# Sheet1.net
KiCad netlist of a schematic drawn in Altium Designer
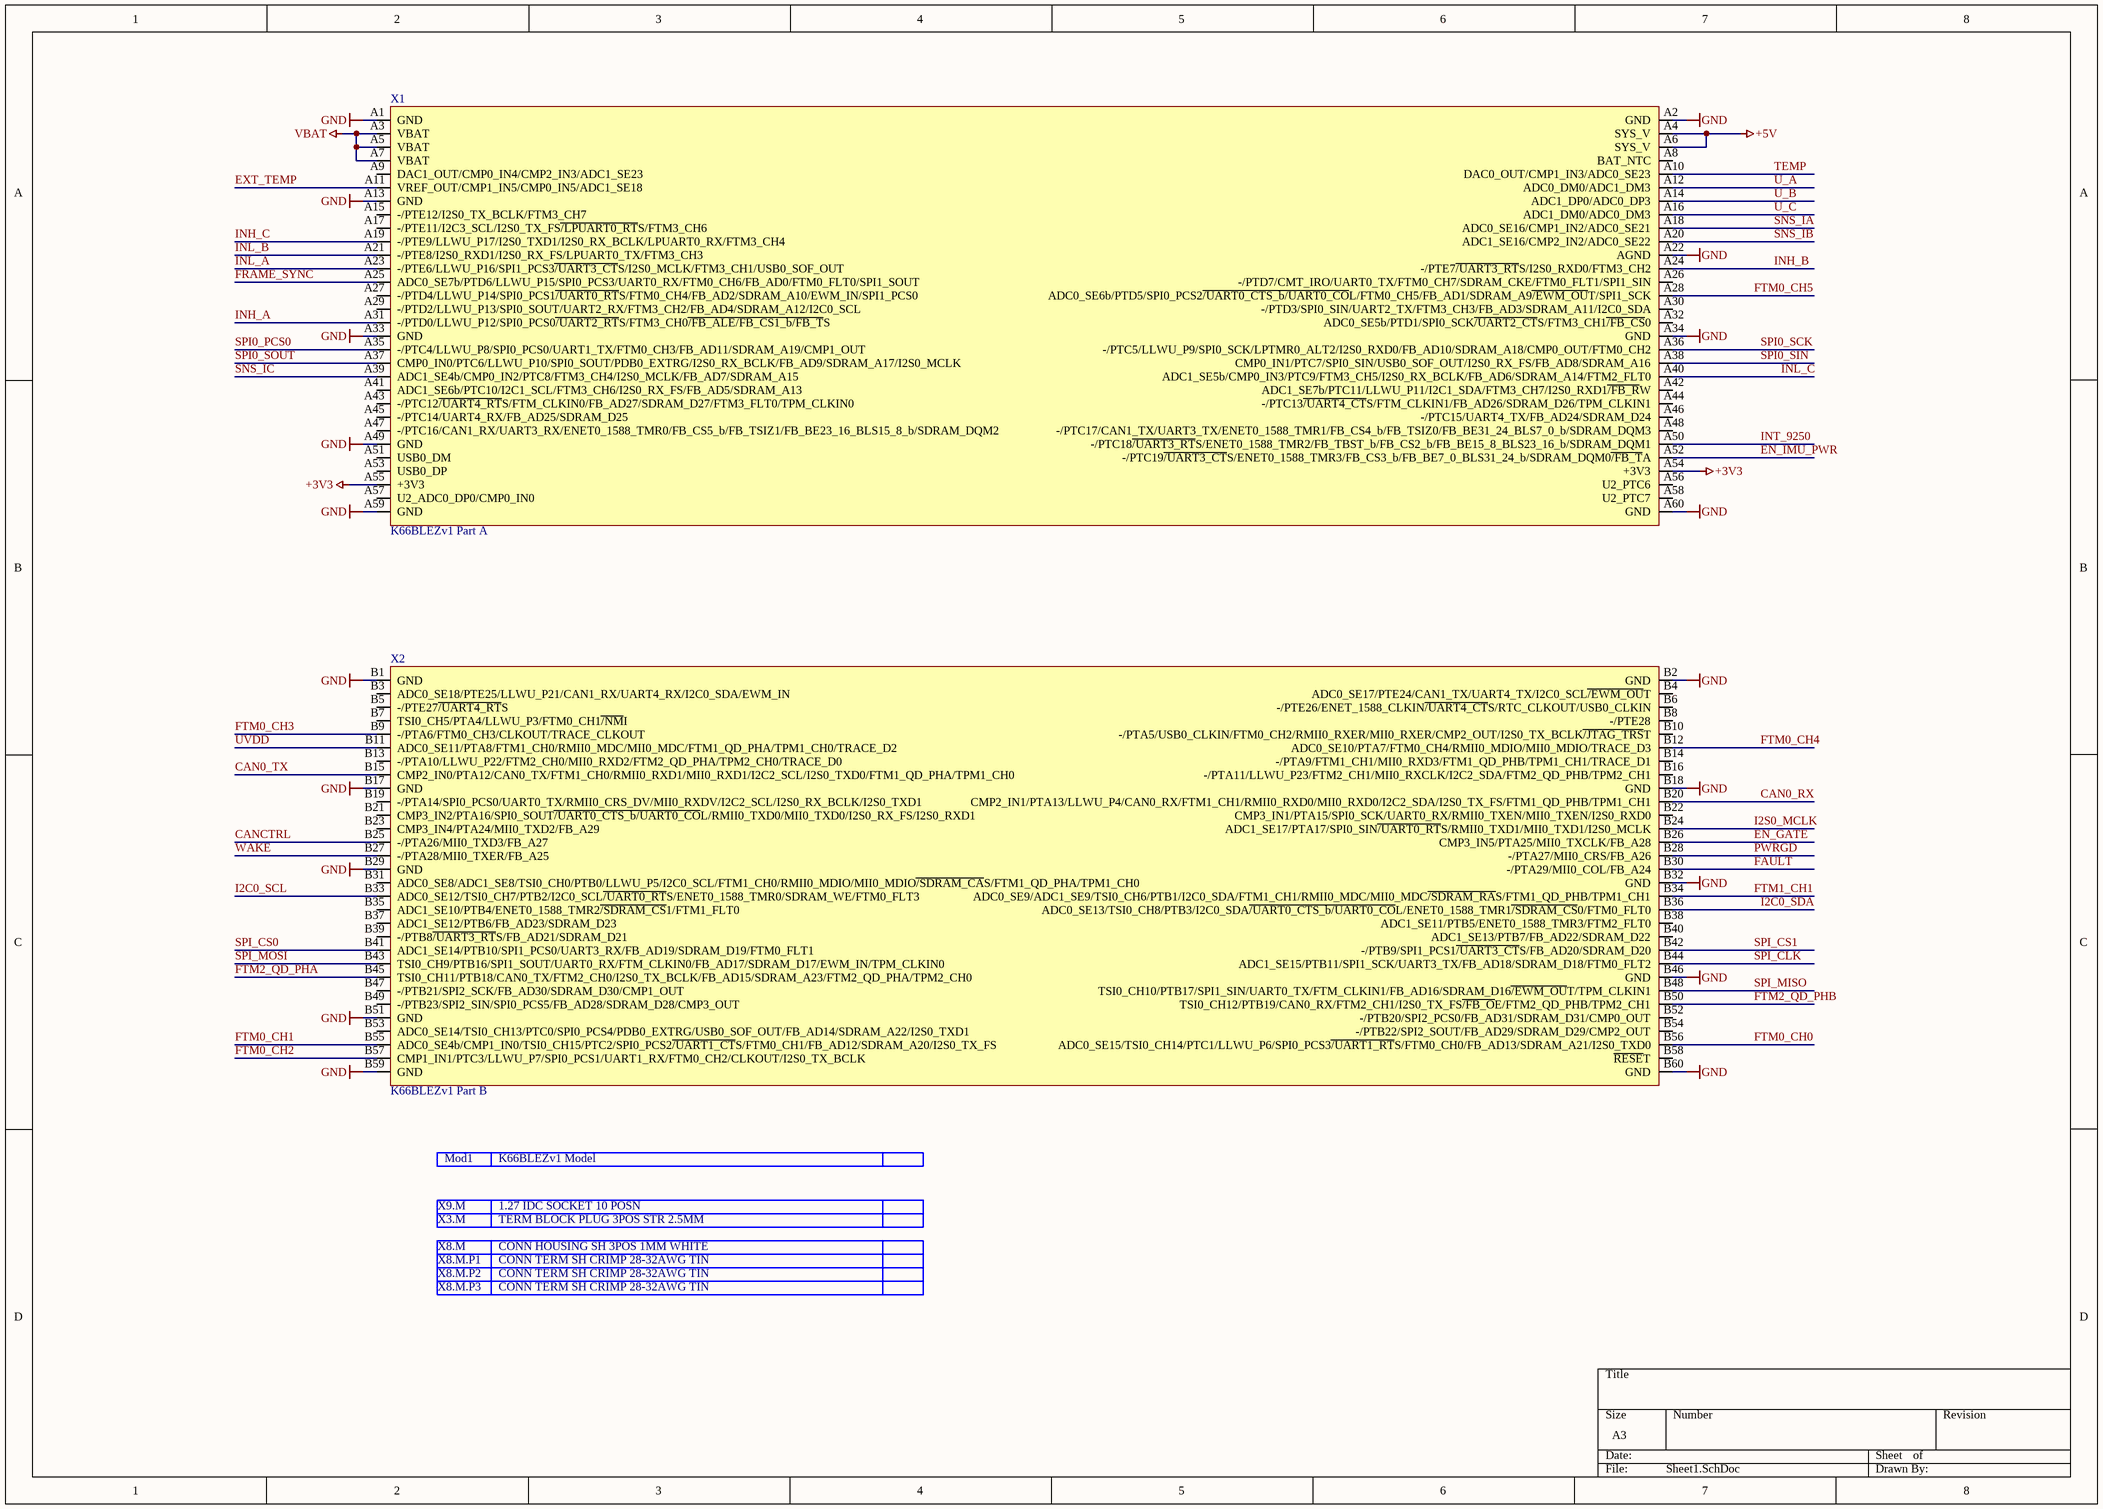
[diagram p0: Sheet1.SchDoc]

(export (version "E")
  (design (tool "Eeschema 10.0.6"))
  (components
    (comp (ref "Mod1")
      (value "K66BLEZv1 Model")
      (footprint "K66BLEZv1.0 Mechanical")
      (libsource (lib "K66BLEZ1") (part "K66BLEZv1 Model"))
    )
    (comp (ref "X1")
      (value "K66BLEZv1 Part A")
      (footprint "K66BLEZv1.0 Part A")
      (description "60 Position Connector Header, Outer Shroud Contacts Surface Mount Gold")
      (fields (field (name "MANUFACTURER") "Hirose Electric Co Ltd") (field (name "PARTNUM") "H10787-ND"))
      (libsource (lib "K66BLEZ1") (part "K66BLEZv1 Part A"))
    )
    (comp (ref "X2")
      (value "K66BLEZv1 Part B")
      (footprint "K66BLEZv1.0 Part B")
      (description "60 Position Connector Header, Outer Shroud Contacts Surface Mount Gold")
      (fields (field (name "MANUFACTURER") "Hirose Electric Co Ltd") (field (name "PARTNUM") "H10787-ND"))
      (libsource (lib "K66BLEZ1") (part "K66BLEZv1 Part B"))
    )
    (comp (ref "X3.M")
      (value "TERM BLOCK PLUG 3POS STR 2.5MM")
      (description "3 Position Terminal Block Plug, Female Sockets 0.098\" (2.50mm) 180° Free Hanging (In-Line)")
      (fields (field (name "MANUFACTURER") "Phoenix Contact") (field (name "PARTNUM") "277-11811-ND"))
      (libsource (lib "ea_Mechanical") (part "BOM item"))
    )
    (comp (ref "X8.M")
      (value "CONN HOUSING SH 3POS 1MM WHITE")
      (description "3 Position Rectangular Housing Connector Receptacle Natural 0.039\" (1.00mm)")
      (fields (field (name "MANUFACTURER") "JST Sales America Inc.") (field (name "PARTNUM") "455-1393-ND"))
      (libsource (lib "ea_Mechanical") (part "BOM item"))
    )
    (comp (ref "X8.M.P1")
      (value "CONN TERM SH CRIMP 28-32AWG TIN")
      (description "Contact Crimp Socket 28-32 AWG Tin")
      (fields (field (name "MANUFACTURER") "JST Sales America Inc.") (field (name "PARTNUM") "455-1561-1-ND"))
      (libsource (lib "ea_Mechanical") (part "BOM item"))
    )
    (comp (ref "X8.M.P2")
      (value "CONN TERM SH CRIMP 28-32AWG TIN")
      (description "Contact Crimp Socket 28-32 AWG Tin")
      (fields (field (name "MANUFACTURER") "JST Sales America Inc.") (field (name "PARTNUM") "455-1561-1-ND"))
      (libsource (lib "ea_Mechanical") (part "BOM item"))
    )
    (comp (ref "X8.M.P3")
      (value "CONN TERM SH CRIMP 28-32AWG TIN")
      (description "Contact Crimp Socket 28-32 AWG Tin")
      (fields (field (name "MANUFACTURER") "JST Sales America Inc.") (field (name "PARTNUM") "455-1561-1-ND"))
      (libsource (lib "ea_Mechanical") (part "BOM item"))
    )
    (comp (ref "X9.M")
      (value "1.27 IDC SOCKET 10 POSN")
      (description "10 Position Rectangular Receptacle Connector IDC Gold 30 AWG")
      (fields (field (name "MANUFACTURER") "CNC Tech") (field (name "PARTNUM") "1175-1645-ND"))
      (libsource (lib "ea_Mechanical") (part "BOM item"))
    )
  )
  (nets
    (net (code "1") (name "+3V3") (class "Default")
      (node (ref "X1") (pin "A54") (pinfunction "+3V3_A54") (pintype "passive"))
      (node (ref "X1") (pin "A55") (pinfunction "+3V3_A55") (pintype "passive"))
    )
    (net (code "2") (name "+5V") (class "Default")
      (node (ref "X1") (pin "A4") (pinfunction "SYS_V_A4") (pintype "passive"))
      (node (ref "X1") (pin "A6") (pinfunction "SYS_V_A6") (pintype "passive"))
    )
    (net (code "3") (name "/CAN0_RX") (class "Default")
      (node (ref "X2") (pin "B20") (pinfunction "CMP2_IN1/PTA13/LLWU_P4/CAN0_RX/FTM1_CH1/RMII0_RXD0/MII0_RXD0/I2C2_SDA/I2S0_TX_FS/FTM1_QD_PHB/TPM1_CH1_B20") (pintype "bidirectional"))
    )
    (net (code "4") (name "/CAN0_TX") (class "Default")
      (node (ref "X2") (pin "B15") (pinfunction "CMP2_IN0/PTA12/CAN0_TX/FTM1_CH0/RMII0_RXD1/MII0_RXD1/I2C2_SCL/I2S0_TXD0/FTM1_QD_PHA/TPM1_CH0_B15") (pintype "bidirectional"))
    )
    (net (code "5") (name "/CANCTRL") (class "Default")
      (node (ref "X2") (pin "B25") (pinfunction "-/PTA26/MII0_TXD3/FB_A27_B25") (pintype "bidirectional"))
    )
    (net (code "6") (name "/EN_GATE") (class "Default")
      (node (ref "X2") (pin "B26") (pinfunction "CMP3_IN5/PTA25/MII0_TXCLK/FB_A28_B26") (pintype "bidirectional"))
    )
    (net (code "7") (name "/EN_IMU_PWR") (class "Default")
      (node (ref "X1") (pin "A52") (pinfunction "-/PTC19~{/UART3_CT}S/ENET0_1588_TMR3/FB_CS3_b/FB_BE7_0_BLS31_24_b/SDRAM_DQM0~{/FB_T}A_A52") (pintype "bidirectional"))
    )
    (net (code "8") (name "/EXT_TEMP") (class "Default")
      (node (ref "X1") (pin "A11") (pinfunction "VREF_OUT/CMP1_IN5/CMP0_IN5/ADC1_SE18_A11") (pintype "bidirectional"))
    )
    (net (code "9") (name "/FAULT") (class "Default")
      (node (ref "X2") (pin "B30") (pinfunction "-/PTA29/MII0_COL/FB_A24_B30") (pintype "bidirectional"))
    )
    (net (code "10") (name "/FRAME_SYNC") (class "Default")
      (node (ref "X1") (pin "A25") (pinfunction "ADC0_SE7b/PTD6/LLWU_P15/SPI0_PCS3/UART0_RX/FTM0_CH6/FB_AD0/FTM0_FLT0/SPI1_SOUT_A25") (pintype "bidirectional"))
    )
    (net (code "11") (name "/FTM0_CH0") (class "Default")
      (node (ref "X2") (pin "B56") (pinfunction "ADC0_SE15/TSI0_CH14/PTC1/LLWU_P6/SPI0_PCS3~{/UART1_RT}S/FTM0_CH0/FB_AD13/SDRAM_A21/I2S0_TXD0_B56") (pintype "bidirectional"))
    )
    (net (code "12") (name "/FTM0_CH1") (class "Default")
      (node (ref "X2") (pin "B55") (pinfunction "ADC0_SE4b/CMP1_IN0/TSI0_CH15/PTC2/SPI0_PCS2~{/UART1_CT}S/FTM0_CH1/FB_AD12/SDRAM_A20/I2S0_TX_FS_B55") (pintype "bidirectional"))
    )
    (net (code "13") (name "/FTM0_CH2") (class "Default")
      (node (ref "X2") (pin "B57") (pinfunction "CMP1_IN1/PTC3/LLWU_P7/SPI0_PCS1/UART1_RX/FTM0_CH2/CLKOUT/I2S0_TX_BCLK_B57") (pintype "bidirectional"))
    )
    (net (code "14") (name "/FTM0_CH3") (class "Default")
      (node (ref "X2") (pin "B9") (pinfunction "-/PTA6/FTM0_CH3/CLKOUT/TRACE_CLKOUT_B9") (pintype "bidirectional"))
    )
    (net (code "15") (name "/FTM0_CH4") (class "Default")
      (node (ref "X2") (pin "B12") (pinfunction "ADC0_SE10/PTA7/FTM0_CH4/RMII0_MDIO/MII0_MDIO/TRACE_D3_B12") (pintype "bidirectional"))
    )
    (net (code "16") (name "/FTM0_CH5") (class "Default")
      (node (ref "X1") (pin "A28") (pinfunction "ADC0_SE6b/PTD5/SPI0_PCS2~{/UART0_CTS_b/UART0_CO}L/FTM0_CH5/FB_AD1/SDRAM_A9~{/EWM_OU}T/SPI1_SCK_A28") (pintype "bidirectional"))
    )
    (net (code "17") (name "/FTM1_CH1") (class "Default")
      (node (ref "X2") (pin "B34") (pinfunction "ADC0_SE9/ADC1_SE9/TSI0_CH6/PTB1/I2C0_SDA/FTM1_CH1/RMII0_MDC/MII0_MDC~{/SDRAM_RA}S/FTM1_QD_PHB/TPM1_CH1_B34") (pintype "bidirectional"))
    )
    (net (code "18") (name "/FTM2_QD_PHA") (class "Default")
      (node (ref "X2") (pin "B45") (pinfunction "TSI0_CH11/PTB18/CAN0_TX/FTM2_CH0/I2S0_TX_BCLK/FB_AD15/SDRAM_A23/FTM2_QD_PHA/TPM2_CH0_B45") (pintype "bidirectional"))
    )
    (net (code "19") (name "/FTM2_QD_PHB") (class "Default")
      (node (ref "X2") (pin "B50") (pinfunction "TSI0_CH12/PTB19/CAN0_RX/FTM2_CH1/I2S0_TX_FS~{/FB_O}E/FTM2_QD_PHB/TPM2_CH1_B50") (pintype "bidirectional"))
    )
    (net (code "20") (name "/I2C0_SCL") (class "Default")
      (node (ref "X2") (pin "B33") (pinfunction "ADC0_SE12/TSI0_CH7/PTB2/I2C0_SCL~{/UART0_RT}S/ENET0_1588_TMR0/SDRAM_WE/FTM0_FLT3_B33") (pintype "bidirectional"))
    )
    (net (code "21") (name "/I2C0_SDA") (class "Default")
      (node (ref "X2") (pin "B36") (pinfunction "ADC0_SE13/TSI0_CH8/PTB3/I2C0_SDA~{/UART0_CTS_b/UART0_CO}L/ENET0_1588_TMR1~{/SDRAM_CS}0/FTM0_FLT0_B36") (pintype "bidirectional"))
    )
    (net (code "22") (name "/I2S0_MCLK") (class "Default")
      (node (ref "X2") (pin "B24") (pinfunction "ADC1_SE17/PTA17/SPI0_SIN~{/UART0_RT}S/RMII0_TXD1/MII0_TXD1/I2S0_MCLK_B24") (pintype "bidirectional"))
    )
    (net (code "23") (name "/INH_A") (class "Default")
      (node (ref "X1") (pin "A31") (pinfunction "-/PTD0/LLWU_P12/SPI0_PCS0~{/UART2_RT}S/FTM3_CH0~{/FB_ALE/FB_CS1_b/FB_T}S_A31") (pintype "bidirectional"))
    )
    (net (code "24") (name "/INH_B") (class "Default")
      (node (ref "X1") (pin "A24") (pinfunction "-/PTE7~{/UART3_RT}S/I2S0_RXD0/FTM3_CH2_A24") (pintype "bidirectional"))
    )
    (net (code "25") (name "/INH_C") (class "Default")
      (node (ref "X1") (pin "A19") (pinfunction "-/PTE9/LLWU_P17/I2S0_TXD1/I2S0_RX_BCLK/LPUART0_RX/FTM3_CH4_A19") (pintype "bidirectional"))
    )
    (net (code "26") (name "/INL_A") (class "Default")
      (node (ref "X1") (pin "A23") (pinfunction "-/PTE6/LLWU_P16/SPI1_PCS3~{/UART3_CT}S/I2S0_MCLK/FTM3_CH1/USB0_SOF_OUT_A23") (pintype "bidirectional"))
    )
    (net (code "27") (name "/INL_B") (class "Default")
      (node (ref "X1") (pin "A21") (pinfunction "-/PTE8/I2S0_RXD1/I2S0_RX_FS/LPUART0_TX/FTM3_CH3_A21") (pintype "bidirectional"))
    )
    (net (code "28") (name "/INL_C") (class "Default")
      (node (ref "X1") (pin "A40") (pinfunction "ADC1_SE5b/CMP0_IN3/PTC9/FTM3_CH5/I2S0_RX_BCLK/FB_AD6/SDRAM_A14/FTM2_FLT0_A40") (pintype "bidirectional"))
    )
    (net (code "29") (name "/INT_9250") (class "Default")
      (node (ref "X1") (pin "A50") (pinfunction "-/PTC18~{/UART3_RT}S/ENET0_1588_TMR2/FB_TBST_b/FB_CS2_b/FB_BE15_8_BLS23_16_b/SDRAM_DQM1_A50") (pintype "bidirectional"))
    )
    (net (code "30") (name "/PWRGD") (class "Default")
      (node (ref "X2") (pin "B28") (pinfunction "-/PTA27/MII0_CRS/FB_A26_B28") (pintype "bidirectional"))
    )
    (net (code "31") (name "/SNS_IA") (class "Default")
      (node (ref "X1") (pin "A18") (pinfunction "ADC0_SE16/CMP1_IN2/ADC0_SE21_A18") (pintype "bidirectional"))
    )
    (net (code "32") (name "/SNS_IB") (class "Default")
      (node (ref "X1") (pin "A20") (pinfunction "ADC1_SE16/CMP2_IN2/ADC0_SE22_A20") (pintype "bidirectional"))
    )
    (net (code "33") (name "/SNS_IC") (class "Default")
      (node (ref "X1") (pin "A39") (pinfunction "ADC1_SE4b/CMP0_IN2/PTC8/FTM3_CH4/I2S0_MCLK/FB_AD7/SDRAM_A15_A39") (pintype "bidirectional"))
    )
    (net (code "34") (name "/SPI0_PCS0") (class "Default")
      (node (ref "X1") (pin "A35") (pinfunction "-/PTC4/LLWU_P8/SPI0_PCS0/UART1_TX/FTM0_CH3/FB_AD11/SDRAM_A19/CMP1_OUT_A35") (pintype "bidirectional"))
    )
    (net (code "35") (name "/SPI0_SCK") (class "Default")
      (node (ref "X1") (pin "A36") (pinfunction "-/PTC5/LLWU_P9/SPI0_SCK/LPTMR0_ALT2/I2S0_RXD0/FB_AD10/SDRAM_A18/CMP0_OUT/FTM0_CH2_A36") (pintype "bidirectional"))
    )
    (net (code "36") (name "/SPI0_SIN") (class "Default")
      (node (ref "X1") (pin "A38") (pinfunction "CMP0_IN1/PTC7/SPI0_SIN/USB0_SOF_OUT/I2S0_RX_FS/FB_AD8/SDRAM_A16_A38") (pintype "bidirectional"))
    )
    (net (code "37") (name "/SPI0_SOUT") (class "Default")
      (node (ref "X1") (pin "A37") (pinfunction "CMP0_IN0/PTC6/LLWU_P10/SPI0_SOUT/PDB0_EXTRG/I2S0_RX_BCLK/FB_AD9/SDRAM_A17/I2S0_MCLK_A37") (pintype "bidirectional"))
    )
    (net (code "38") (name "/SPI_CLK") (class "Default")
      (node (ref "X2") (pin "B44") (pinfunction "ADC1_SE15/PTB11/SPI1_SCK/UART3_TX/FB_AD18/SDRAM_D18/FTM0_FLT2_B44") (pintype "bidirectional"))
    )
    (net (code "39") (name "/SPI_CS0") (class "Default")
      (node (ref "X2") (pin "B41") (pinfunction "ADC1_SE14/PTB10/SPI1_PCS0/UART3_RX/FB_AD19/SDRAM_D19/FTM0_FLT1_B41") (pintype "bidirectional"))
    )
    (net (code "40") (name "/SPI_CS1") (class "Default")
      (node (ref "X2") (pin "B42") (pinfunction "-/PTB9/SPI1_PCS1~{/UART3_CT}S/FB_AD20/SDRAM_D20_B42") (pintype "bidirectional"))
    )
    (net (code "41") (name "/SPI_MISO") (class "Default")
      (node (ref "X2") (pin "B48") (pinfunction "TSI0_CH10/PTB17/SPI1_SIN/UART0_TX/FTM_CLKIN1/FB_AD16/SDRAM_D16~{/EWM_OU}T/TPM_CLKIN1_B48") (pintype "bidirectional"))
    )
    (net (code "42") (name "/SPI_MOSI") (class "Default")
      (node (ref "X2") (pin "B43") (pinfunction "TSI0_CH9/PTB16/SPI1_SOUT/UART0_RX/FTM_CLKIN0/FB_AD17/SDRAM_D17/EWM_IN/TPM_CLKIN0_B43") (pintype "bidirectional"))
    )
    (net (code "43") (name "/TEMP") (class "Default")
      (node (ref "X1") (pin "A10") (pinfunction "DAC0_OUT/CMP1_IN3/ADC0_SE23_A10") (pintype "bidirectional"))
    )
    (net (code "44") (name "/UVDD") (class "Default")
      (node (ref "X2") (pin "B11") (pinfunction "ADC0_SE11/PTA8/FTM1_CH0/RMII0_MDC/MII0_MDC/FTM1_QD_PHA/TPM1_CH0/TRACE_D2_B11") (pintype "bidirectional"))
    )
    (net (code "45") (name "/U_A") (class "Default")
      (node (ref "X1") (pin "A12") (pinfunction "ADC0_DM0/ADC1_DM3_A12") (pintype "bidirectional"))
    )
    (net (code "46") (name "/U_B") (class "Default")
      (node (ref "X1") (pin "A14") (pinfunction "ADC1_DP0/ADC0_DP3_A14") (pintype "bidirectional"))
    )
    (net (code "47") (name "/U_C") (class "Default")
      (node (ref "X1") (pin "A16") (pinfunction "ADC1_DM0/ADC0_DM3_A16") (pintype "bidirectional"))
    )
    (net (code "48") (name "/WAKE") (class "Default")
      (node (ref "X2") (pin "B27") (pinfunction "-/PTA28/MII0_TXER/FB_A25_B27") (pintype "bidirectional"))
    )
    (net (code "49") (name "GND") (class "Default")
      (node (ref "X1") (pin "A1") (pinfunction "GND_A1") (pintype "passive"))
      (node (ref "X1") (pin "A13") (pinfunction "GND_A13") (pintype "passive"))
      (node (ref "X1") (pin "A2") (pinfunction "GND_A2") (pintype "passive"))
      (node (ref "X1") (pin "A22") (pinfunction "AGND_A22") (pintype "passive"))
      (node (ref "X1") (pin "A33") (pinfunction "GND_A33") (pintype "passive"))
      (node (ref "X1") (pin "A34") (pinfunction "GND_A34") (pintype "passive"))
      (node (ref "X1") (pin "A49") (pinfunction "GND_A49") (pintype "passive"))
      (node (ref "X1") (pin "A59") (pinfunction "GND_A59") (pintype "passive"))
      (node (ref "X1") (pin "A60") (pinfunction "GND_A60") (pintype "passive"))
      (node (ref "X2") (pin "B1") (pinfunction "GND_B1") (pintype "passive"))
      (node (ref "X2") (pin "B17") (pinfunction "GND_B17") (pintype "passive"))
      (node (ref "X2") (pin "B18") (pinfunction "GND_B18") (pintype "passive"))
      (node (ref "X2") (pin "B2") (pinfunction "GND_B2") (pintype "passive"))
      (node (ref "X2") (pin "B29") (pinfunction "GND_B29") (pintype "passive"))
      (node (ref "X2") (pin "B32") (pinfunction "GND_B32") (pintype "passive"))
      (node (ref "X2") (pin "B46") (pinfunction "GND_B46") (pintype "passive"))
      (node (ref "X2") (pin "B51") (pinfunction "GND_B51") (pintype "passive"))
      (node (ref "X2") (pin "B59") (pinfunction "GND_B59") (pintype "passive"))
      (node (ref "X2") (pin "B60") (pinfunction "GND_B60") (pintype "passive"))
    )
    (net (code "50") (name "VBAT") (class "Default")
      (node (ref "X1") (pin "A3") (pinfunction "VBAT_A3") (pintype "passive"))
      (node (ref "X1") (pin "A5") (pinfunction "VBAT_A5") (pintype "passive"))
      (node (ref "X1") (pin "A7") (pinfunction "VBAT_A7") (pintype "passive"))
    )
    (net (code "51") (name "unconnected-(Mod1-Pad0)") (class "Default")
      (node (ref "Mod1") (pin "0") (pinfunction "0_0") (pintype "passive"))
    )
    (net (code "52") (name "unconnected-(X1--{slash}PTC12~{{slash}UART4_RT}S{slash}FTM_CLKIN0{slash}FB_AD27{slash}SDRAM_D27{slash}FTM3_FLT0{slash}TPM_CLKIN0-PadA43)") (class "Default")
      (node (ref "X1") (pin "A43") (pinfunction "-/PTC12~{/UART4_RT}S/FTM_CLKIN0/FB_AD27/SDRAM_D27/FTM3_FLT0/TPM_CLKIN0_A43") (pintype "bidirectional"))
    )
    (net (code "53") (name "unconnected-(X1--{slash}PTC13~{{slash}UART4_CT}S{slash}FTM_CLKIN1{slash}FB_AD26{slash}SDRAM_D26{slash}TPM_CLKIN1-PadA44)") (class "Default")
      (node (ref "X1") (pin "A44") (pinfunction "-/PTC13~{/UART4_CT}S/FTM_CLKIN1/FB_AD26/SDRAM_D26/TPM_CLKIN1_A44") (pintype "bidirectional"))
    )
    (net (code "54") (name "unconnected-(X1--{slash}PTC14{slash}UART4_RX{slash}FB_AD25{slash}SDRAM_D25-PadA45)") (class "Default")
      (node (ref "X1") (pin "A45") (pinfunction "-/PTC14/UART4_RX/FB_AD25/SDRAM_D25_A45") (pintype "bidirectional"))
    )
    (net (code "55") (name "unconnected-(X1--{slash}PTC15{slash}UART4_TX{slash}FB_AD24{slash}SDRAM_D24-PadA46)") (class "Default")
      (node (ref "X1") (pin "A46") (pinfunction "-/PTC15/UART4_TX/FB_AD24/SDRAM_D24_A46") (pintype "bidirectional"))
    )
    (net (code "56") (name "unconnected-(X1--{slash}PTC16{slash}CAN1_RX{slash}UART3_RX{slash}ENET0_1588_TMR0{slash}FB_CS5_b{slash}FB_TSIZ1{slash}FB_BE23_16_BLS15_8_b{slash}SDRAM_DQM2-PadA47)") (class "Default")
      (node (ref "X1") (pin "A47") (pinfunction "-/PTC16/CAN1_RX/UART3_RX/ENET0_1588_TMR0/FB_CS5_b/FB_TSIZ1/FB_BE23_16_BLS15_8_b/SDRAM_DQM2_A47") (pintype "bidirectional"))
    )
    (net (code "57") (name "unconnected-(X1--{slash}PTC17{slash}CAN1_TX{slash}UART3_TX{slash}ENET0_1588_TMR1{slash}FB_CS4_b{slash}FB_TSIZ0{slash}FB_BE31_24_BLS7_0_b{slash}SDRAM_DQM3-PadA48)") (class "Default")
      (node (ref "X1") (pin "A48") (pinfunction "-/PTC17/CAN1_TX/UART3_TX/ENET0_1588_TMR1/FB_CS4_b/FB_TSIZ0/FB_BE31_24_BLS7_0_b/SDRAM_DQM3_A48") (pintype "bidirectional"))
    )
    (net (code "58") (name "unconnected-(X1--{slash}PTD2{slash}LLWU_P13{slash}SPI0_SOUT{slash}UART2_RX{slash}FTM3_CH2{slash}FB_AD4{slash}SDRAM_A12{slash}I2C0_SCL-PadA29)") (class "Default")
      (node (ref "X1") (pin "A29") (pinfunction "-/PTD2/LLWU_P13/SPI0_SOUT/UART2_RX/FTM3_CH2/FB_AD4/SDRAM_A12/I2C0_SCL_A29") (pintype "bidirectional"))
    )
    (net (code "59") (name "unconnected-(X1--{slash}PTD3{slash}SPI0_SIN{slash}UART2_TX{slash}FTM3_CH3{slash}FB_AD3{slash}SDRAM_A11{slash}I2C0_SDA-PadA30)") (class "Default")
      (node (ref "X1") (pin "A30") (pinfunction "-/PTD3/SPI0_SIN/UART2_TX/FTM3_CH3/FB_AD3/SDRAM_A11/I2C0_SDA_A30") (pintype "bidirectional"))
    )
    (net (code "60") (name "unconnected-(X1--{slash}PTD4{slash}LLWU_P14{slash}SPI0_PCS1~{{slash}UART0_RT}S{slash}FTM0_CH4{slash}FB_AD2{slash}SDRAM_A10{slash}EWM_IN{slash}SPI1_PCS0-PadA27)") (class "Default")
      (node (ref "X1") (pin "A27") (pinfunction "-/PTD4/LLWU_P14/SPI0_PCS1~{/UART0_RT}S/FTM0_CH4/FB_AD2/SDRAM_A10/EWM_IN/SPI1_PCS0_A27") (pintype "bidirectional"))
    )
    (net (code "61") (name "unconnected-(X1--{slash}PTD7{slash}CMT_IRO{slash}UART0_TX{slash}FTM0_CH7{slash}SDRAM_CKE{slash}FTM0_FLT1{slash}SPI1_SIN-PadA26)") (class "Default")
      (node (ref "X1") (pin "A26") (pinfunction "-/PTD7/CMT_IRO/UART0_TX/FTM0_CH7/SDRAM_CKE/FTM0_FLT1/SPI1_SIN_A26") (pintype "bidirectional"))
    )
    (net (code "62") (name "unconnected-(X1--{slash}PTE11{slash}I2C3_SCL{slash}I2S0_TX_FS~{{slash}LPUART0_RT}S{slash}FTM3_CH6-PadA17)") (class "Default")
      (node (ref "X1") (pin "A17") (pinfunction "-/PTE11/I2C3_SCL/I2S0_TX_FS~{/LPUART0_RT}S/FTM3_CH6_A17") (pintype "bidirectional"))
    )
    (net (code "63") (name "unconnected-(X1--{slash}PTE12{slash}I2S0_TX_BCLK{slash}FTM3_CH7-PadA15)") (class "Default")
      (node (ref "X1") (pin "A15") (pinfunction "-/PTE12/I2S0_TX_BCLK/FTM3_CH7_A15") (pintype "bidirectional"))
    )
    (net (code "64") (name "unconnected-(X1-ADC0_SE5b{slash}PTD1{slash}SPI0_SCK~{{slash}UART2_CT}S{slash}FTM3_CH1~{{slash}FB_CS}0-PadA32)") (class "Default")
      (node (ref "X1") (pin "A32") (pinfunction "ADC0_SE5b/PTD1/SPI0_SCK~{/UART2_CT}S/FTM3_CH1~{/FB_CS}0_A32") (pintype "bidirectional"))
    )
    (net (code "65") (name "unconnected-(X1-ADC1_SE6b{slash}PTC10{slash}I2C1_SCL{slash}FTM3_CH6{slash}I2S0_RX_FS{slash}FB_AD5{slash}SDRAM_A13-PadA41)") (class "Default")
      (node (ref "X1") (pin "A41") (pinfunction "ADC1_SE6b/PTC10/I2C1_SCL/FTM3_CH6/I2S0_RX_FS/FB_AD5/SDRAM_A13_A41") (pintype "bidirectional"))
    )
    (net (code "66") (name "unconnected-(X1-ADC1_SE7b{slash}PTC11{slash}LLWU_P11{slash}I2C1_SDA{slash}FTM3_CH7{slash}I2S0_RXD1~{{slash}FB_R}W-PadA42)") (class "Default")
      (node (ref "X1") (pin "A42") (pinfunction "ADC1_SE7b/PTC11/LLWU_P11/I2C1_SDA/FTM3_CH7/I2S0_RXD1~{/FB_R}W_A42") (pintype "bidirectional"))
    )
    (net (code "67") (name "unconnected-(X1-BAT_NTC-PadA8)") (class "Default")
      (node (ref "X1") (pin "A8") (pinfunction "BAT_NTC_A8") (pintype "passive"))
    )
    (net (code "68") (name "unconnected-(X1-DAC1_OUT{slash}CMP0_IN4{slash}CMP2_IN3{slash}ADC1_SE23-PadA9)") (class "Default")
      (node (ref "X1") (pin "A9") (pinfunction "DAC1_OUT/CMP0_IN4/CMP2_IN3/ADC1_SE23_A9") (pintype "bidirectional"))
    )
    (net (code "69") (name "unconnected-(X1-U2_ADC0_DP0{slash}CMP0_IN0-PadA57)") (class "Default")
      (node (ref "X1") (pin "A57") (pinfunction "U2_ADC0_DP0/CMP0_IN0_A57") (pintype "passive"))
    )
    (net (code "70") (name "unconnected-(X1-U2_PTC6-PadA56)") (class "Default")
      (node (ref "X1") (pin "A56") (pinfunction "U2_PTC6_A56") (pintype "passive"))
    )
    (net (code "71") (name "unconnected-(X1-U2_PTC7-PadA58)") (class "Default")
      (node (ref "X1") (pin "A58") (pinfunction "U2_PTC7_A58") (pintype "passive"))
    )
    (net (code "72") (name "unconnected-(X1-USB0_DM-PadA51)") (class "Default")
      (node (ref "X1") (pin "A51") (pinfunction "USB0_DM_A51") (pintype "bidirectional"))
    )
    (net (code "73") (name "unconnected-(X1-USB0_DP-PadA53)") (class "Default")
      (node (ref "X1") (pin "A53") (pinfunction "USB0_DP_A53") (pintype "bidirectional"))
    )
    (net (code "74") (name "unconnected-(X2--{slash}PTA5{slash}USB0_CLKIN{slash}FTM0_CH2{slash}RMII0_RXER{slash}MII0_RXER{slash}CMP2_OUT{slash}I2S0_TX_BCLK~{{slash}JTAG_TRS}T-PadB10)") (class "Default")
      (node (ref "X2") (pin "B10") (pinfunction "-/PTA5/USB0_CLKIN/FTM0_CH2/RMII0_RXER/MII0_RXER/CMP2_OUT/I2S0_TX_BCLK~{/JTAG_TRS}T_B10") (pintype "bidirectional"))
    )
    (net (code "75") (name "unconnected-(X2--{slash}PTA9{slash}FTM1_CH1{slash}MII0_RXD3{slash}FTM1_QD_PHB{slash}TPM1_CH1{slash}TRACE_D1-PadB14)") (class "Default")
      (node (ref "X2") (pin "B14") (pinfunction "-/PTA9/FTM1_CH1/MII0_RXD3/FTM1_QD_PHB/TPM1_CH1/TRACE_D1_B14") (pintype "bidirectional"))
    )
    (net (code "76") (name "unconnected-(X2--{slash}PTA10{slash}LLWU_P22{slash}FTM2_CH0{slash}MII0_RXD2{slash}FTM2_QD_PHA{slash}TPM2_CH0{slash}TRACE_D0-PadB13)") (class "Default")
      (node (ref "X2") (pin "B13") (pinfunction "-/PTA10/LLWU_P22/FTM2_CH0/MII0_RXD2/FTM2_QD_PHA/TPM2_CH0/TRACE_D0_B13") (pintype "bidirectional"))
    )
    (net (code "77") (name "unconnected-(X2--{slash}PTA11{slash}LLWU_P23{slash}FTM2_CH1{slash}MII0_RXCLK{slash}I2C2_SDA{slash}FTM2_QD_PHB{slash}TPM2_CH1-PadB16)") (class "Default")
      (node (ref "X2") (pin "B16") (pinfunction "-/PTA11/LLWU_P23/FTM2_CH1/MII0_RXCLK/I2C2_SDA/FTM2_QD_PHB/TPM2_CH1_B16") (pintype "bidirectional"))
    )
    (net (code "78") (name "unconnected-(X2--{slash}PTA14{slash}SPI0_PCS0{slash}UART0_TX{slash}RMII0_CRS_DV{slash}MII0_RXDV{slash}I2C2_SCL{slash}I2S0_RX_BCLK{slash}I2S0_TXD1-PadB19)") (class "Default")
      (node (ref "X2") (pin "B19") (pinfunction "-/PTA14/SPI0_PCS0/UART0_TX/RMII0_CRS_DV/MII0_RXDV/I2C2_SCL/I2S0_RX_BCLK/I2S0_TXD1_B19") (pintype "bidirectional"))
    )
    (net (code "79") (name "unconnected-(X2--{slash}PTB8~{{slash}UART3_RT}S{slash}FB_AD21{slash}SDRAM_D21-PadB39)") (class "Default")
      (node (ref "X2") (pin "B39") (pinfunction "-/PTB8~{/UART3_RT}S/FB_AD21/SDRAM_D21_B39") (pintype "bidirectional"))
    )
    (net (code "80") (name "unconnected-(X2--{slash}PTB20{slash}SPI2_PCS0{slash}FB_AD31{slash}SDRAM_D31{slash}CMP0_OUT-PadB52)") (class "Default")
      (node (ref "X2") (pin "B52") (pinfunction "-/PTB20/SPI2_PCS0/FB_AD31/SDRAM_D31/CMP0_OUT_B52") (pintype "bidirectional"))
    )
    (net (code "81") (name "unconnected-(X2--{slash}PTB21{slash}SPI2_SCK{slash}FB_AD30{slash}SDRAM_D30{slash}CMP1_OUT-PadB47)") (class "Default")
      (node (ref "X2") (pin "B47") (pinfunction "-/PTB21/SPI2_SCK/FB_AD30/SDRAM_D30/CMP1_OUT_B47") (pintype "bidirectional"))
    )
    (net (code "82") (name "unconnected-(X2--{slash}PTB22{slash}SPI2_SOUT{slash}FB_AD29{slash}SDRAM_D29{slash}CMP2_OUT-PadB54)") (class "Default")
      (node (ref "X2") (pin "B54") (pinfunction "-/PTB22/SPI2_SOUT/FB_AD29/SDRAM_D29/CMP2_OUT_B54") (pintype "bidirectional"))
    )
    (net (code "83") (name "unconnected-(X2--{slash}PTB23{slash}SPI2_SIN{slash}SPI0_PCS5{slash}FB_AD28{slash}SDRAM_D28{slash}CMP3_OUT-PadB49)") (class "Default")
      (node (ref "X2") (pin "B49") (pinfunction "-/PTB23/SPI2_SIN/SPI0_PCS5/FB_AD28/SDRAM_D28/CMP3_OUT_B49") (pintype "bidirectional"))
    )
    (net (code "84") (name "unconnected-(X2--{slash}PTE26{slash}ENET_1588_CLKIN~{{slash}UART4_CT}S{slash}RTC_CLKOUT{slash}USB0_CLKIN-PadB6)") (class "Default")
      (node (ref "X2") (pin "B6") (pinfunction "-/PTE26/ENET_1588_CLKIN~{/UART4_CT}S/RTC_CLKOUT/USB0_CLKIN_B6") (pintype "bidirectional"))
    )
    (net (code "85") (name "unconnected-(X2--{slash}PTE27~{{slash}UART4_RT}S-PadB5)") (class "Default")
      (node (ref "X2") (pin "B5") (pinfunction "-/PTE27~{/UART4_RT}S_B5") (pintype "bidirectional"))
    )
    (net (code "86") (name "unconnected-(X2--{slash}PTE28-PadB8)") (class "Default")
      (node (ref "X2") (pin "B8") (pinfunction "-/PTE28_B8") (pintype "bidirectional"))
    )
    (net (code "87") (name "unconnected-(X2-ADC0_SE8{slash}ADC1_SE8{slash}TSI0_CH0{slash}PTB0{slash}LLWU_P5{slash}I2C0_SCL{slash}FTM1_CH0{slash}RMII0_MDIO{slash}MII0_MDIO~{{slash}SDRAM_CA}S{slash}FTM1_QD_PHA{slash}TPM1_CH0-PadB31)") (class "Default")
      (node (ref "X2") (pin "B31") (pinfunction "ADC0_SE8/ADC1_SE8/TSI0_CH0/PTB0/LLWU_P5/I2C0_SCL/FTM1_CH0/RMII0_MDIO/MII0_MDIO~{/SDRAM_CA}S/FTM1_QD_PHA/TPM1_CH0_B31") (pintype "bidirectional"))
    )
    (net (code "88") (name "unconnected-(X2-ADC0_SE14{slash}TSI0_CH13{slash}PTC0{slash}SPI0_PCS4{slash}PDB0_EXTRG{slash}USB0_SOF_OUT{slash}FB_AD14{slash}SDRAM_A22{slash}I2S0_TXD1-PadB53)") (class "Default")
      (node (ref "X2") (pin "B53") (pinfunction "ADC0_SE14/TSI0_CH13/PTC0/SPI0_PCS4/PDB0_EXTRG/USB0_SOF_OUT/FB_AD14/SDRAM_A22/I2S0_TXD1_B53") (pintype "bidirectional"))
    )
    (net (code "89") (name "unconnected-(X2-ADC0_SE17{slash}PTE24{slash}CAN1_TX{slash}UART4_TX{slash}I2C0_SCL~{{slash}EWM_OU}T-PadB4)") (class "Default")
      (node (ref "X2") (pin "B4") (pinfunction "ADC0_SE17/PTE24/CAN1_TX/UART4_TX/I2C0_SCL~{/EWM_OU}T_B4") (pintype "bidirectional"))
    )
    (net (code "90") (name "unconnected-(X2-ADC0_SE18{slash}PTE25{slash}LLWU_P21{slash}CAN1_RX{slash}UART4_RX{slash}I2C0_SDA{slash}EWM_IN-PadB3)") (class "Default")
      (node (ref "X2") (pin "B3") (pinfunction "ADC0_SE18/PTE25/LLWU_P21/CAN1_RX/UART4_RX/I2C0_SDA/EWM_IN_B3") (pintype "bidirectional"))
    )
    (net (code "91") (name "unconnected-(X2-ADC1_SE10{slash}PTB4{slash}ENET0_1588_TMR2~{{slash}SDRAM_CS}1{slash}FTM1_FLT0-PadB35)") (class "Default")
      (node (ref "X2") (pin "B35") (pinfunction "ADC1_SE10/PTB4/ENET0_1588_TMR2~{/SDRAM_CS}1/FTM1_FLT0_B35") (pintype "bidirectional"))
    )
    (net (code "92") (name "unconnected-(X2-ADC1_SE11{slash}PTB5{slash}ENET0_1588_TMR3{slash}FTM2_FLT0-PadB38)") (class "Default")
      (node (ref "X2") (pin "B38") (pinfunction "ADC1_SE11/PTB5/ENET0_1588_TMR3/FTM2_FLT0_B38") (pintype "bidirectional"))
    )
    (net (code "93") (name "unconnected-(X2-ADC1_SE12{slash}PTB6{slash}FB_AD23{slash}SDRAM_D23-PadB37)") (class "Default")
      (node (ref "X2") (pin "B37") (pinfunction "ADC1_SE12/PTB6/FB_AD23/SDRAM_D23_B37") (pintype "bidirectional"))
    )
    (net (code "94") (name "unconnected-(X2-ADC1_SE13{slash}PTB7{slash}FB_AD22{slash}SDRAM_D22-PadB40)") (class "Default")
      (node (ref "X2") (pin "B40") (pinfunction "ADC1_SE13/PTB7/FB_AD22/SDRAM_D22_B40") (pintype "bidirectional"))
    )
    (net (code "95") (name "unconnected-(X2-CMP3_IN1{slash}PTA15{slash}SPI0_SCK{slash}UART0_RX{slash}RMII0_TXEN{slash}MII0_TXEN{slash}I2S0_RXD0-PadB22)") (class "Default")
      (node (ref "X2") (pin "B22") (pinfunction "CMP3_IN1/PTA15/SPI0_SCK/UART0_RX/RMII0_TXEN/MII0_TXEN/I2S0_RXD0_B22") (pintype "bidirectional"))
    )
    (net (code "96") (name "unconnected-(X2-CMP3_IN2{slash}PTA16{slash}SPI0_SOUT~{{slash}UART0_CTS_b{slash}UART0_CO}L{slash}RMII0_TXD0{slash}MII0_TXD0{slash}I2S0_RX_FS{slash}I2S0_RXD1-PadB21)") (class "Default")
      (node (ref "X2") (pin "B21") (pinfunction "CMP3_IN2/PTA16/SPI0_SOUT~{/UART0_CTS_b/UART0_CO}L/RMII0_TXD0/MII0_TXD0/I2S0_RX_FS/I2S0_RXD1_B21") (pintype "bidirectional"))
    )
    (net (code "97") (name "unconnected-(X2-CMP3_IN4{slash}PTA24{slash}MII0_TXD2{slash}FB_A29-PadB23)") (class "Default")
      (node (ref "X2") (pin "B23") (pinfunction "CMP3_IN4/PTA24/MII0_TXD2/FB_A29_B23") (pintype "bidirectional"))
    )
    (net (code "98") (name "unconnected-(X2-TSI0_CH5{slash}PTA4{slash}LLWU_P3{slash}FTM0_CH1~{{slash}NM}I-PadB7)") (class "Default")
      (node (ref "X2") (pin "B7") (pinfunction "TSI0_CH5/PTA4/LLWU_P3/FTM0_CH1~{/NM}I_B7") (pintype "bidirectional"))
    )
    (net (code "99") (name "unconnected-(X2-~{RESE}T-PadB58)") (class "Default")
      (node (ref "X2") (pin "B58") (pinfunction "~{RESE}T_B58") (pintype "bidirectional"))
    )
    (net (code "100") (name "unconnected-(X3.M-Pad0)") (class "Default")
      (node (ref "X3.M") (pin "0") (pinfunction "0_0") (pintype "passive"))
    )
    (net (code "101") (name "unconnected-(X8.M-Pad0)") (class "Default")
      (node (ref "X8.M") (pin "0") (pinfunction "0_0") (pintype "passive"))
    )
    (net (code "102") (name "unconnected-(X8.M.P1-Pad0)") (class "Default")
      (node (ref "X8.M.P1") (pin "0") (pinfunction "0_0") (pintype "passive"))
    )
    (net (code "103") (name "unconnected-(X8.M.P2-Pad0)") (class "Default")
      (node (ref "X8.M.P2") (pin "0") (pinfunction "0_0") (pintype "passive"))
    )
    (net (code "104") (name "unconnected-(X8.M.P3-Pad0)") (class "Default")
      (node (ref "X8.M.P3") (pin "0") (pinfunction "0_0") (pintype "passive"))
    )
    (net (code "105") (name "unconnected-(X9.M-Pad0)") (class "Default")
      (node (ref "X9.M") (pin "0") (pinfunction "0_0") (pintype "passive"))
    )
  )
)
